# Analog.net
KiCad netlist of a schematic drawn in Altium Designer
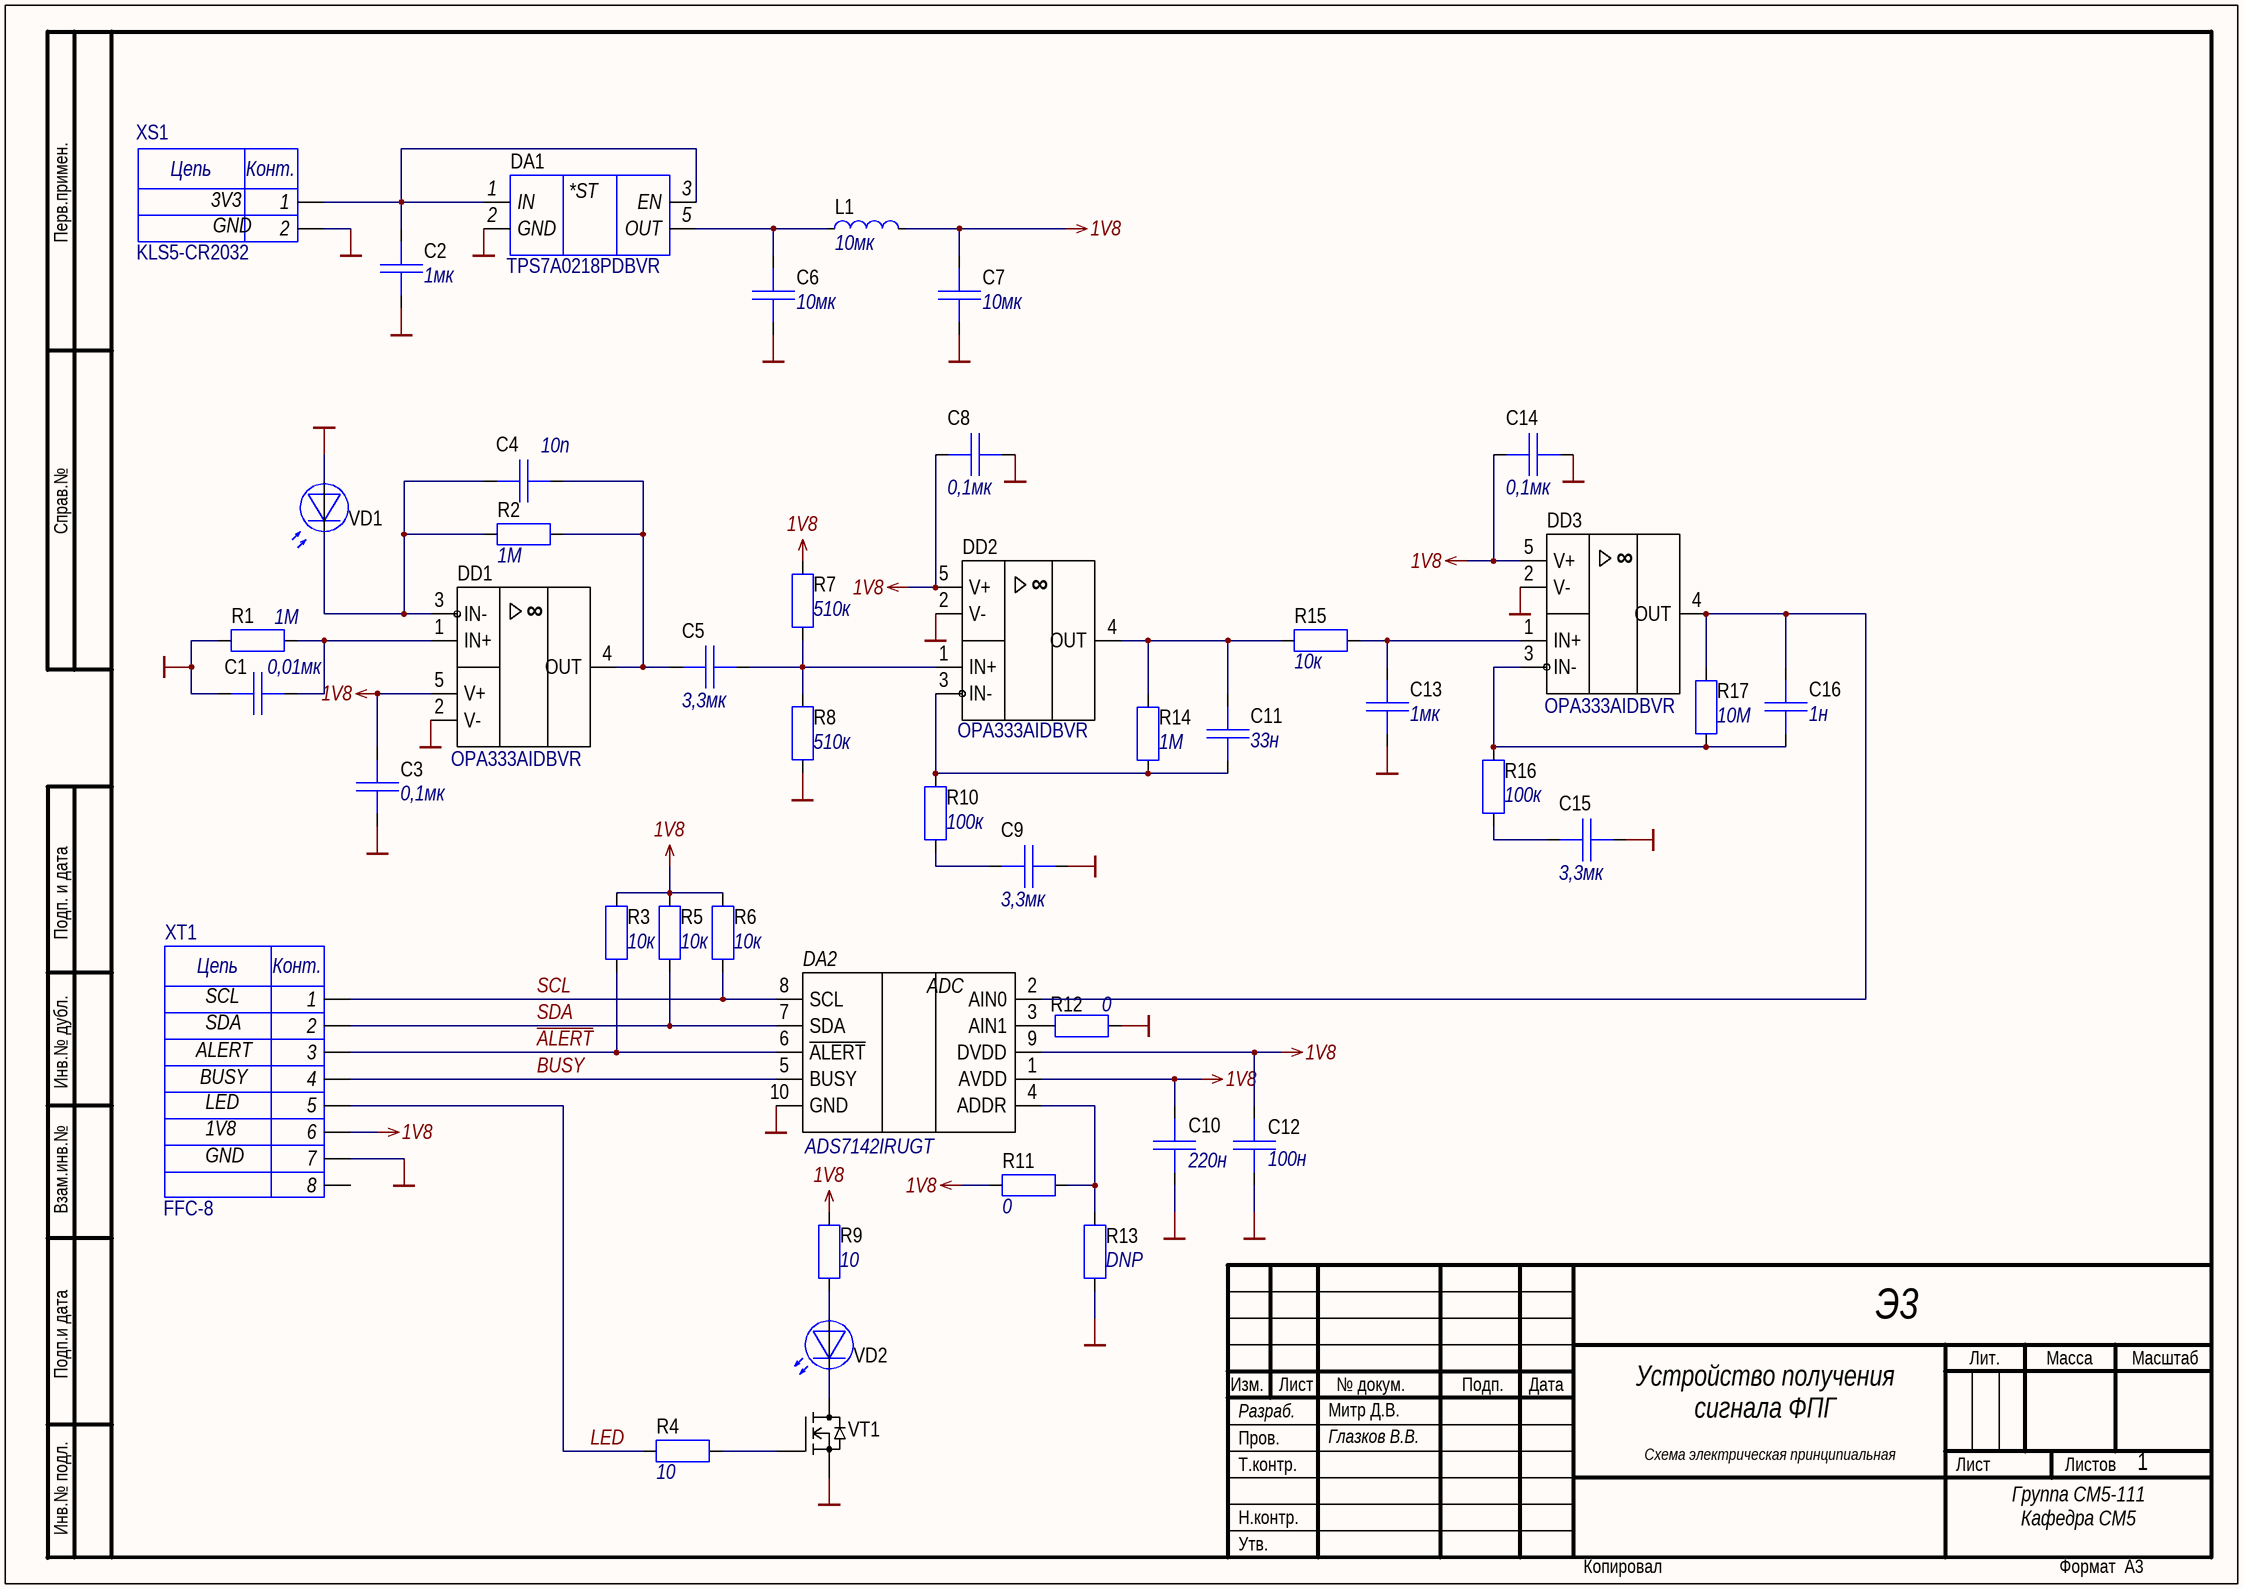
[diagram p0: Analog.SchDoc]

(export (version "E")
  (design (tool "Eeschema 10.0.6"))
  (components
    (comp (ref "C1")
      (value "0,01мк")
      (footprint "cap0402")
      (description "Керамический конденсатор")
      (libsource (lib "RSL10_SchLib") (part "CapCer"))
    )
    (comp (ref "C2")
      (value "1мк")
      (footprint "cap0603")
      (description "Керамический конденсатор")
      (libsource (lib "RSL10_SchLib") (part "CapCer"))
    )
    (comp (ref "C3")
      (value "0,1мк")
      (footprint "cap0402")
      (description "Керамический конденсатор")
      (libsource (lib "RSL10_SchLib") (part "CapCer"))
    )
    (comp (ref "C4")
      (value "10п")
      (footprint "cap0402")
      (description "Керамический конденсатор")
      (libsource (lib "RSL10_SchLib") (part "CapCer"))
    )
    (comp (ref "C5")
      (value "3,3мк")
      (footprint "CAP0805")
      (description "Керамический конденсатор")
      (libsource (lib "RSL10_SchLib") (part "CapCer"))
    )
    (comp (ref "C6")
      (value "10мк")
      (footprint "cap0603")
      (description "Керамический конденсатор")
      (libsource (lib "RSL10_SchLib") (part "CapCer"))
    )
    (comp (ref "C7")
      (value "10мк")
      (footprint "cap0603")
      (description "Керамический конденсатор")
      (libsource (lib "RSL10_SchLib") (part "CapCer"))
    )
    (comp (ref "C8")
      (value "0,1мк")
      (footprint "cap0402")
      (description "Керамический конденсатор")
      (libsource (lib "RSL10_SchLib") (part "CapCer"))
    )
    (comp (ref "C9")
      (value "3,3мк")
      (footprint "CAP0805")
      (description "Керамический конденсатор")
      (libsource (lib "RSL10_SchLib") (part "CapCer"))
    )
    (comp (ref "C10")
      (value "220н")
      (footprint "cap0402")
      (description "Керамический конденсатор")
      (libsource (lib "RSL10_SchLib") (part "CapCer"))
    )
    (comp (ref "C11")
      (value "33н")
      (footprint "cap0402")
      (description "Керамический конденсатор")
      (libsource (lib "RSL10_SchLib") (part "CapCer"))
    )
    (comp (ref "C12")
      (value "100н")
      (footprint "cap0402")
      (description "Керамический конденсатор")
      (libsource (lib "RSL10_SchLib") (part "CapCer"))
    )
    (comp (ref "C13")
      (value "1мк")
      (footprint "cap0402")
      (description "Керамический конденсатор")
      (libsource (lib "RSL10_SchLib") (part "CapCer"))
    )
    (comp (ref "C14")
      (value "0,1мк")
      (footprint "cap0402")
      (description "Керамический конденсатор")
      (libsource (lib "RSL10_SchLib") (part "CapCer"))
    )
    (comp (ref "C15")
      (value "3,3мк")
      (footprint "CAP0805")
      (description "Керамический конденсатор")
      (libsource (lib "RSL10_SchLib") (part "CapCer"))
    )
    (comp (ref "C16")
      (value "1н")
      (footprint "cap0402")
      (description "Керамический конденсатор")
      (libsource (lib "RSL10_SchLib") (part "CapCer"))
    )
    (comp (ref "DA1")
      (value "TPS7A0218PDBVR")
      (footprint "TPS7A02")
      (fields (field (name "NAME_MAIN") "TPS7A0218PDBVR"))
      (libsource (lib "RSL10_SchLib") (part "LDO"))
    )
    (comp (ref "DA2")
      (value "ADC")
      (footprint "ADS7142IRUGT")
      (fields (field (name "MAIN_NAME") "ADS7142IRUGT"))
      (libsource (lib "RSL10_SchLib") (part "ADC"))
    )
    (comp (ref "DD1")
      (value "operational amplifier_2")
      (footprint "OPA333")
      (description "Операционный усилитель")
      (fields (field (name "MAIN_NAME") "OPA333AIDBVR"))
      (libsource (lib "RSL10_SchLib") (part "operational amplifier_2"))
    )
    (comp (ref "DD2")
      (value "operational amplifier_1")
      (footprint "OPA333")
      (description "Операционный усилитель")
      (fields (field (name "MAIN_NAME") "OPA333AIDBVR"))
      (libsource (lib "RSL10_SchLib") (part "operational amplifier_1"))
    )
    (comp (ref "DD3")
      (value "operational amplifier_1")
      (footprint "OPA333")
      (description "Операционный усилитель")
      (fields (field (name "MAIN_NAME") "OPA333AIDBVR"))
      (libsource (lib "RSL10_SchLib") (part "operational amplifier_1"))
    )
    (comp (ref "L1")
      (value "10мк")
      (footprint "MLZ1608M100WT000")
      (description "Катушка индуктивности")
      (libsource (lib "RSL10_SchLib") (part "Ind"))
    )
    (comp (ref "R1")
      (value "1M")
      (footprint "RES0402")
      (description "Резистор")
      (fields (field (name "TOLERANCE") "1%") (field (name "MANUFACTURER") "АЛЯР.434110.005ТУ"))
      (libsource (lib "") (part "Res_3"))
    )
    (comp (ref "R2")
      (value "1M")
      (footprint "RES0402")
      (description "Резистор")
      (fields (field (name "MANUFACTURER") "АЛЯР.434110.005ТУ"))
      (libsource (lib "") (part "Res_3"))
    )
    (comp (ref "R3")
      (value "10к")
      (footprint "RES0402")
      (description "Резистор")
      (fields (field (name "TOLERANCE") "5%") (field (name "MANUFACTURER") "АЛЯР.434110.005ТУ"))
      (libsource (lib "") (part "Res_2"))
    )
    (comp (ref "R4")
      (value "10")
      (footprint "RES0402")
      (description "Резистор")
      (fields (field (name "TOLERANCE") "5%") (field (name "MANUFACTURER") "АЛЯР.434110.005ТУ"))
      (libsource (lib "RSL10_SchLib") (part "Res"))
    )
    (comp (ref "R5")
      (value "10к")
      (footprint "RES0402")
      (description "Резистор")
      (fields (field (name "TOLERANCE") "5%") (field (name "MANUFACTURER") "АЛЯР.434110.005ТУ"))
      (libsource (lib "") (part "Res_2"))
    )
    (comp (ref "R6")
      (value "10к")
      (footprint "RES0402")
      (description "Резистор")
      (fields (field (name "TOLERANCE") "5%") (field (name "MANUFACTURER") "АЛЯР.434110.005ТУ"))
      (libsource (lib "") (part "Res_2"))
    )
    (comp (ref "R7")
      (value "510к")
      (footprint "RES0402")
      (description "Резистор")
      (fields (field (name "MANUFACTURER") "АЛЯР.434110.005ТУ"))
      (libsource (lib "") (part "Res_1"))
    )
    (comp (ref "R8")
      (value "510к")
      (footprint "RES0402")
      (description "Резистор")
      (fields (field (name "MANUFACTURER") "АЛЯР.434110.005ТУ"))
      (libsource (lib "") (part "Res_1"))
    )
    (comp (ref "R9")
      (value "10")
      (footprint "RES0402")
      (description "Резистор")
      (fields (field (name "TOLERANCE") "5%") (field (name "MANUFACTURER") "АЛЯР.434110.005ТУ"))
      (libsource (lib "") (part "Res_3"))
    )
    (comp (ref "R10")
      (value "100к")
      (footprint "RES0402")
      (description "Резистор")
      (fields (field (name "MANUFACTURER") "АЛЯР.434110.005ТУ"))
      (libsource (lib "RSL10_SchLib") (part "Res"))
    )
    (comp (ref "R11")
      (value "0")
      (footprint "RES0402")
      (description "Резистор")
      (fields (field (name "TOLERANCE") "5%") (field (name "MANUFACTURER") "АЛЯР.434110.005ТУ"))
      (libsource (lib "") (part "Res_3"))
    )
    (comp (ref "R12")
      (value "0")
      (footprint "RES0402")
      (description "Резистор")
      (fields (field (name "TOLERANCE") "5%") (field (name "MANUFACTURER") "АЛЯР.434110.005ТУ"))
      (libsource (lib "") (part "Res_3"))
    )
    (comp (ref "R13")
      (value "DNP")
      (footprint "RES0402")
      (description "Резистор")
      (fields (field (name "TOLERANCE") "5%") (field (name "MANUFACTURER") "АЛЯР.434110.005ТУ"))
      (libsource (lib "") (part "Res_2"))
    )
    (comp (ref "R14")
      (value "1М")
      (footprint "RES0402")
      (description "Резистор")
      (fields (field (name "TOLERANCE") "1%") (field (name "MANUFACTURER") "АЛЯР.434110.005ТУ"))
      (libsource (lib "RSL10_SchLib") (part "Res"))
    )
    (comp (ref "R15")
      (value "10к")
      (footprint "RES0402")
      (description "Резистор")
      (fields (field (name "TOLERANCE") "5%") (field (name "MANUFACTURER") "АЛЯР.434110.005ТУ"))
      (libsource (lib "RSL10_SchLib") (part "Res"))
    )
    (comp (ref "R16")
      (value "100к")
      (footprint "RES0402")
      (description "Резистор")
      (fields (field (name "MANUFACTURER") "АЛЯР.434110.005ТУ"))
      (libsource (lib "RSL10_SchLib") (part "Res"))
    )
    (comp (ref "R17")
      (value "10М")
      (footprint "RES0402")
      (description "Резистор")
      (fields (field (name "MANUFACTURER") "АЛЯР.434110.005ТУ"))
      (libsource (lib "RSL10_SchLib") (part "Res"))
    )
    (comp (ref "VD1")
      (value "3Л341БаА0.339.189ТУ")
      (footprint "SFH2703")
      (description "Photodiode")
      (libsource (lib "RSL10_SchLib") (part "Photodiode"))
    )
    (comp (ref "VD2")
      (value "15412094A9000аА0.339.189ТУ")
      (footprint "LED1206")
      (description "Излучатель")
      (libsource (lib "RSL10_SchLib") (part "Led"))
    )
    (comp (ref "VT1")
      (value "RU1J002YNTCL")
      (footprint "Mosfet")
      (description "N-MOSFET DirectFET SQ")
      (libsource (lib "RSL10_SchLib") (part "RU1J002YNTCL"))
    )
    (comp (ref "XS1")
      (value "KLS5-CR2032БСАР.430420.014ТУ")
      (footprint "Battery")
      (fields (field (name "NAME_MAIN") "KLS5-CR2032"))
      (libsource (lib "RSL10_SchLib") (part "CR2032"))
    )
    (comp (ref "XT1")
      (value "FFC-82328702-8")
      (footprint "FFC8")
      (fields (field (name "NAME_MAIN") "FFC-8"))
      (libsource (lib "RSL10_SchLib") (part "FFC8"))
    )
  )
  (nets
    (net (code "1") (name "/BUSY") (class "Default")
      (node (ref "DA2") (pin "5") (pinfunction "BUSY_5") (pintype "passive"))
      (node (ref "XT1") (pin "4") (pinfunction "4_4") (pintype "passive"))
    )
    (net (code "2") (name "/LED") (class "Default")
      (node (ref "R4") (pin "2") (pinfunction "2_2") (pintype "passive"))
      (node (ref "XT1") (pin "5") (pinfunction "5_5") (pintype "passive"))
    )
    (net (code "3") (name "/SCL") (class "Default")
      (node (ref "DA2") (pin "8") (pinfunction "SCL_8") (pintype "passive"))
      (node (ref "R6") (pin "2") (pinfunction "2_2") (pintype "passive"))
      (node (ref "XT1") (pin "1") (pinfunction "1_1") (pintype "passive"))
    )
    (net (code "4") (name "/SDA") (class "Default")
      (node (ref "DA2") (pin "7") (pinfunction "SDA_7") (pintype "passive"))
      (node (ref "R5") (pin "2") (pinfunction "2_2") (pintype "passive"))
      (node (ref "XT1") (pin "2") (pinfunction "2_2") (pintype "passive"))
    )
    (net (code "5") (name "/~{ALERT}") (class "Default")
      (node (ref "DA2") (pin "6") (pinfunction "~{ALERT}_6") (pintype "passive"))
      (node (ref "R3") (pin "2") (pinfunction "2_2") (pintype "passive"))
      (node (ref "XT1") (pin "3") (pinfunction "3_3") (pintype "passive"))
    )
    (net (code "6") (name "1V8") (class "Default")
      (node (ref "C10") (pin "2") (pinfunction "2_2") (pintype "passive"))
      (node (ref "C12") (pin "2") (pinfunction "2_2") (pintype "passive"))
      (node (ref "C14") (pin "2") (pinfunction "2_2") (pintype "passive"))
      (node (ref "C3") (pin "2") (pinfunction "2_2") (pintype "passive"))
      (node (ref "C7") (pin "2") (pinfunction "2_2") (pintype "passive"))
      (node (ref "C8") (pin "2") (pinfunction "2_2") (pintype "passive"))
      (node (ref "DA2") (pin "1") (pinfunction "AVDD_1") (pintype "passive"))
      (node (ref "DA2") (pin "9") (pinfunction "DVDD_9") (pintype "passive"))
      (node (ref "DD1") (pin "5") (pinfunction "V+_5") (pintype "passive"))
      (node (ref "DD2") (pin "5") (pinfunction "V+_5") (pintype "passive"))
      (node (ref "DD3") (pin "5") (pinfunction "V+_5") (pintype "passive"))
      (node (ref "L1") (pin "2") (pinfunction "2_2") (pintype "passive"))
      (node (ref "R11") (pin "1") (pinfunction "1_1") (pintype "passive"))
      (node (ref "R3") (pin "1") (pinfunction "1_1") (pintype "passive"))
      (node (ref "R5") (pin "1") (pinfunction "1_1") (pintype "passive"))
      (node (ref "R6") (pin "1") (pinfunction "1_1") (pintype "passive"))
      (node (ref "R7") (pin "2") (pinfunction "2_2") (pintype "passive"))
      (node (ref "R9") (pin "2") (pinfunction "2_2") (pintype "passive"))
      (node (ref "XT1") (pin "6") (pinfunction "6_6") (pintype "passive"))
    )
    (net (code "7") (name "GND") (class "Default")
      (node (ref "C1") (pin "1") (pinfunction "1_1") (pintype "passive"))
      (node (ref "C10") (pin "1") (pinfunction "1_1") (pintype "passive"))
      (node (ref "C12") (pin "1") (pinfunction "1_1") (pintype "passive"))
      (node (ref "C13") (pin "1") (pinfunction "1_1") (pintype "passive"))
      (node (ref "C14") (pin "1") (pinfunction "1_1") (pintype "passive"))
      (node (ref "C15") (pin "2") (pinfunction "2_2") (pintype "passive"))
      (node (ref "C2") (pin "1") (pinfunction "1_1") (pintype "passive"))
      (node (ref "C3") (pin "1") (pinfunction "1_1") (pintype "passive"))
      (node (ref "C6") (pin "1") (pinfunction "1_1") (pintype "passive"))
      (node (ref "C7") (pin "1") (pinfunction "1_1") (pintype "passive"))
      (node (ref "C8") (pin "1") (pinfunction "1_1") (pintype "passive"))
      (node (ref "C9") (pin "2") (pinfunction "2_2") (pintype "passive"))
      (node (ref "DA1") (pin "2") (pinfunction "GND_2") (pintype "passive"))
      (node (ref "DA2") (pin "10") (pinfunction "GND_10") (pintype "passive"))
      (node (ref "DD1") (pin "2") (pinfunction "V-_2") (pintype "passive"))
      (node (ref "DD2") (pin "2") (pinfunction "V-_2") (pintype "passive"))
      (node (ref "DD3") (pin "2") (pinfunction "V-_2") (pintype "passive"))
      (node (ref "R1") (pin "1") (pinfunction "1_1") (pintype "passive"))
      (node (ref "R12") (pin "2") (pinfunction "2_2") (pintype "passive"))
      (node (ref "R13") (pin "2") (pinfunction "2_2") (pintype "passive"))
      (node (ref "R8") (pin "1") (pinfunction "1_1") (pintype "passive"))
      (node (ref "VD1") (pin "1") (pinfunction "1_1") (pintype "passive"))
      (node (ref "VT1") (pin "2") (pinfunction "S_2") (pintype "power_in"))
      (node (ref "XS1") (pin "2") (pinfunction "2_2") (pintype "passive"))
      (node (ref "XT1") (pin "7") (pinfunction "7_7") (pintype "passive"))
    )
    (net (code "8") (name "Net-(C9-Pad1)") (class "Default")
      (node (ref "C9") (pin "1") (pinfunction "1_1") (pintype "passive"))
      (node (ref "R10") (pin "2") (pinfunction "2_2") (pintype "passive"))
    )
    (net (code "9") (name "Net-(C15-Pad1)") (class "Default")
      (node (ref "C15") (pin "1") (pinfunction "1_1") (pintype "passive"))
      (node (ref "R16") (pin "2") (pinfunction "2_2") (pintype "passive"))
    )
    (net (code "10") (name "Net-(DA1-EN)") (class "Default")
      (node (ref "C2") (pin "2") (pinfunction "2_2") (pintype "passive"))
      (node (ref "DA1") (pin "1") (pinfunction "IN_1") (pintype "passive"))
      (node (ref "DA1") (pin "3") (pinfunction "EN_3") (pintype "passive"))
      (node (ref "XS1") (pin "1") (pinfunction "1_1") (pintype "passive"))
    )
    (net (code "11") (name "Net-(DA1-OUT)") (class "Default")
      (node (ref "C6") (pin "2") (pinfunction "2_2") (pintype "passive"))
      (node (ref "DA1") (pin "5") (pinfunction "OUT_5") (pintype "passive"))
      (node (ref "L1") (pin "1") (pinfunction "1_1") (pintype "passive"))
    )
    (net (code "12") (name "Net-(DA2-ADDR)") (class "Default")
      (node (ref "DA2") (pin "4") (pinfunction "ADDR_4") (pintype "passive"))
      (node (ref "R11") (pin "2") (pinfunction "2_2") (pintype "passive"))
      (node (ref "R13") (pin "1") (pinfunction "1_1") (pintype "passive"))
    )
    (net (code "13") (name "Net-(DA2-AIN0)") (class "Default")
      (node (ref "C16") (pin "1") (pinfunction "1_1") (pintype "passive"))
      (node (ref "DA2") (pin "2") (pinfunction "AIN0_2") (pintype "passive"))
      (node (ref "DD3") (pin "4") (pinfunction "OUT_4") (pintype "passive"))
      (node (ref "R17") (pin "1") (pinfunction "1_1") (pintype "passive"))
    )
    (net (code "14") (name "Net-(DA2-AIN1)") (class "Default")
      (node (ref "DA2") (pin "3") (pinfunction "AIN1_3") (pintype "passive"))
      (node (ref "R12") (pin "1") (pinfunction "1_1") (pintype "passive"))
    )
    (net (code "15") (name "Net-(DD1-IN+)") (class "Default")
      (node (ref "C1") (pin "2") (pinfunction "2_2") (pintype "passive"))
      (node (ref "DD1") (pin "1") (pinfunction "IN+_1") (pintype "passive"))
      (node (ref "R1") (pin "2") (pinfunction "2_2") (pintype "passive"))
    )
    (net (code "16") (name "Net-(DD1-IN-)") (class "Default")
      (node (ref "C4") (pin "1") (pinfunction "1_1") (pintype "passive"))
      (node (ref "DD1") (pin "3") (pinfunction "IN-_3") (pintype "passive"))
      (node (ref "R2") (pin "1") (pinfunction "1_1") (pintype "passive"))
      (node (ref "VD1") (pin "2") (pinfunction "2_2") (pintype "passive"))
    )
    (net (code "17") (name "Net-(DD1-OUT)") (class "Default")
      (node (ref "C4") (pin "2") (pinfunction "2_2") (pintype "passive"))
      (node (ref "C5") (pin "1") (pinfunction "1_1") (pintype "passive"))
      (node (ref "DD1") (pin "4") (pinfunction "OUT_4") (pintype "passive"))
      (node (ref "R2") (pin "2") (pinfunction "2_2") (pintype "passive"))
    )
    (net (code "18") (name "Net-(DD2-IN+)") (class "Default")
      (node (ref "C5") (pin "2") (pinfunction "2_2") (pintype "passive"))
      (node (ref "DD2") (pin "1") (pinfunction "IN+_1") (pintype "passive"))
      (node (ref "R7") (pin "1") (pinfunction "1_1") (pintype "passive"))
      (node (ref "R8") (pin "2") (pinfunction "2_2") (pintype "passive"))
    )
    (net (code "19") (name "Net-(DD2-IN-)") (class "Default")
      (node (ref "C11") (pin "2") (pinfunction "2_2") (pintype "passive"))
      (node (ref "DD2") (pin "3") (pinfunction "IN-_3") (pintype "passive"))
      (node (ref "R10") (pin "1") (pinfunction "1_1") (pintype "passive"))
      (node (ref "R14") (pin "2") (pinfunction "2_2") (pintype "passive"))
    )
    (net (code "20") (name "Net-(DD2-OUT)") (class "Default")
      (node (ref "C11") (pin "1") (pinfunction "1_1") (pintype "passive"))
      (node (ref "DD2") (pin "4") (pinfunction "OUT_4") (pintype "passive"))
      (node (ref "R14") (pin "1") (pinfunction "1_1") (pintype "passive"))
      (node (ref "R15") (pin "2") (pinfunction "2_2") (pintype "passive"))
    )
    (net (code "21") (name "Net-(DD3-IN+)") (class "Default")
      (node (ref "C13") (pin "2") (pinfunction "2_2") (pintype "passive"))
      (node (ref "DD3") (pin "1") (pinfunction "IN+_1") (pintype "passive"))
      (node (ref "R15") (pin "1") (pinfunction "1_1") (pintype "passive"))
    )
    (net (code "22") (name "Net-(DD3-IN-)") (class "Default")
      (node (ref "C16") (pin "2") (pinfunction "2_2") (pintype "passive"))
      (node (ref "DD3") (pin "3") (pinfunction "IN-_3") (pintype "passive"))
      (node (ref "R16") (pin "1") (pinfunction "1_1") (pintype "passive"))
      (node (ref "R17") (pin "2") (pinfunction "2_2") (pintype "passive"))
    )
    (net (code "23") (name "Net-(R9-Pad1)") (class "Default")
      (node (ref "R9") (pin "1") (pinfunction "1_1") (pintype "passive"))
      (node (ref "VD2") (pin "A") (pinfunction "A_A") (pintype "passive"))
    )
    (net (code "24") (name "Net-(VT1-D)") (class "Default")
      (node (ref "VD2") (pin "K") (pinfunction "K_K") (pintype "passive"))
      (node (ref "VT1") (pin "3") (pinfunction "D_3") (pintype "power_in"))
    )
    (net (code "25") (name "Net-(VT1-G)") (class "Default")
      (node (ref "R4") (pin "1") (pinfunction "1_1") (pintype "passive"))
      (node (ref "VT1") (pin "1") (pinfunction "G_1") (pintype "power_in"))
    )
    (net (code "26") (name "unconnected-(XT1-Pad8)") (class "Default")
      (node (ref "XT1") (pin "8") (pinfunction "8_8") (pintype "passive"))
    )
  )
)
